# unicorn_1.net
KiCad netlist of a schematic drawn in Altium Designer
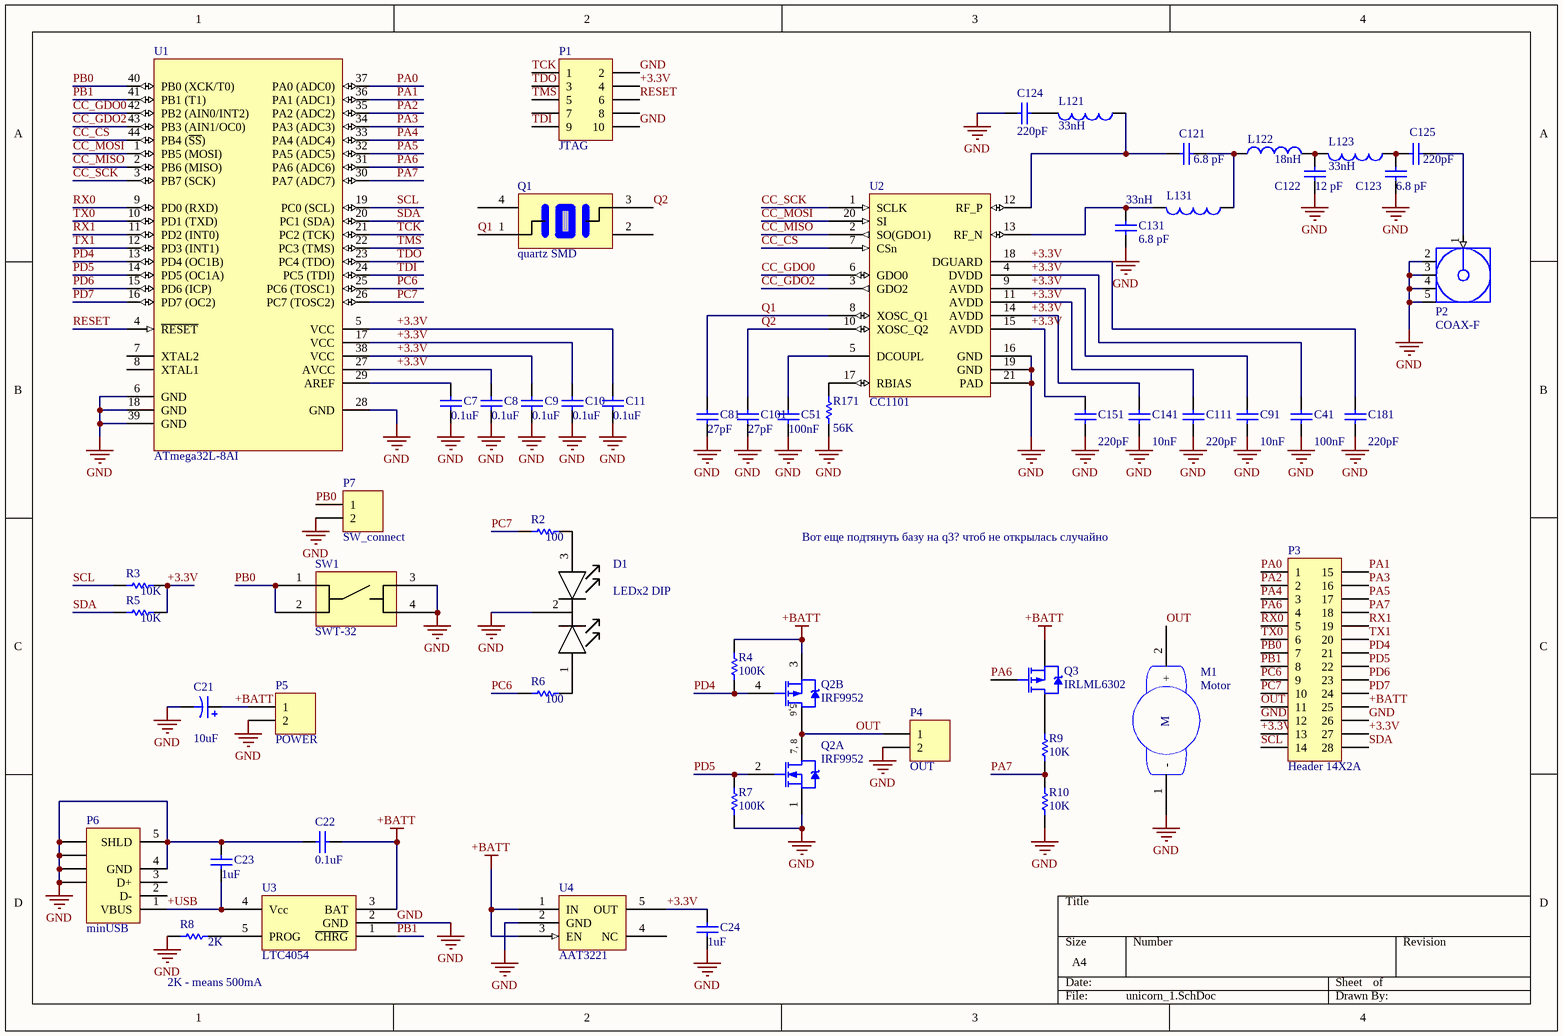
[diagram p0: unicorn_1.SchDoc]

(export (version "E")
  (design (tool "Eeschema 10.0.6"))
  (components
    (comp (ref "C7")
      (value "0.1uF")
      (footprint "CAPC1005L")
      (description "Capacitor (Semiconductor SIM Model)")
      (fields (field (name "PUBLISHER") "Altium Limited"))
      (libsource (lib "Miscellaneous Devices") (part "Cap Semi"))
    )
    (comp (ref "C8")
      (value "0.1uF")
      (footprint "CAPC1005L")
      (description "Capacitor (Semiconductor SIM Model)")
      (fields (field (name "PUBLISHER") "Altium Limited"))
      (libsource (lib "Miscellaneous Devices") (part "Cap Semi"))
    )
    (comp (ref "C9")
      (value "0.1uF")
      (footprint "CAPC1005L")
      (description "Capacitor (Semiconductor SIM Model)")
      (fields (field (name "PUBLISHER") "Altium Limited"))
      (libsource (lib "Miscellaneous Devices") (part "Cap Semi"))
    )
    (comp (ref "C10")
      (value "0.1uF")
      (footprint "CAPC1005L")
      (description "Capacitor (Semiconductor SIM Model)")
      (fields (field (name "PUBLISHER") "Altium Limited"))
      (libsource (lib "Miscellaneous Devices") (part "Cap Semi"))
    )
    (comp (ref "C11")
      (value "0.1uF")
      (footprint "CAPC1005L")
      (description "Capacitor (Semiconductor SIM Model)")
      (fields (field (name "PUBLISHER") "Altium Limited"))
      (libsource (lib "Miscellaneous Devices") (part "Cap Semi"))
    )
    (comp (ref "C21")
      (value "10uF")
      (footprint "CAPC2012L")
      (description "Polarized Capacitor (Surface Mount)")
      (fields (field (name "PUBLISHER") "Altium Limited"))
      (libsource (lib "Miscellaneous Devices") (part "Cap Pol3"))
    )
    (comp (ref "C22")
      (value "0.1uF")
      (footprint "CAPC1005L")
      (description "Capacitor (Semiconductor SIM Model)")
      (fields (field (name "PUBLISHER") "Altium Limited"))
      (libsource (lib "Miscellaneous Devices") (part "Cap Semi"))
    )
    (comp (ref "C23")
      (value "1uF")
      (footprint "CAPC1608L")
      (description "Capacitor (Semiconductor SIM Model)")
      (fields (field (name "PUBLISHER") "Altium Limited"))
      (libsource (lib "Miscellaneous Devices") (part "Cap Semi"))
    )
    (comp (ref "C24")
      (value "1uF")
      (footprint "CAPC1608L")
      (description "Capacitor (Semiconductor SIM Model)")
      (fields (field (name "PUBLISHER") "Altium Limited"))
      (libsource (lib "Miscellaneous Devices") (part "Cap Semi"))
    )
    (comp (ref "C41")
      (value "100nF")
      (footprint "CAPC1005L")
      (description "Capacitor (Semiconductor SIM Model)")
      (fields (field (name "PUBLISHER") "Altium Limited"))
      (libsource (lib "Miscellaneous Devices") (part "Cap Semi"))
    )
    (comp (ref "C51")
      (value "100nF")
      (footprint "CAPC1005L")
      (description "Capacitor (Semiconductor SIM Model)")
      (fields (field (name "PUBLISHER") "Altium Limited"))
      (libsource (lib "Miscellaneous Devices") (part "Cap Semi"))
    )
    (comp (ref "C81")
      (value "27pF")
      (footprint "CAPC1005L")
      (description "Capacitor (Semiconductor SIM Model)")
      (fields (field (name "PUBLISHER") "Altium Limited"))
      (libsource (lib "Miscellaneous Devices") (part "Cap Semi"))
    )
    (comp (ref "C91")
      (value "10nF")
      (footprint "CAPC1005L")
      (description "Capacitor (Semiconductor SIM Model)")
      (fields (field (name "PUBLISHER") "Altium Limited"))
      (libsource (lib "Miscellaneous Devices") (part "Cap Semi"))
    )
    (comp (ref "C101")
      (value "27pF")
      (footprint "CAPC1005L")
      (description "Capacitor (Semiconductor SIM Model)")
      (fields (field (name "PUBLISHER") "Altium Limited"))
      (libsource (lib "Miscellaneous Devices") (part "Cap Semi"))
    )
    (comp (ref "C111")
      (value "220pF")
      (footprint "CAPC1005L")
      (description "Capacitor (Semiconductor SIM Model)")
      (fields (field (name "PUBLISHER") "Altium Limited"))
      (libsource (lib "Miscellaneous Devices") (part "Cap Semi"))
    )
    (comp (ref "C121")
      (value "6.8 pF")
      (footprint "CAPC1005L")
      (description "Capacitor (Semiconductor SIM Model)")
      (fields (field (name "PUBLISHER") "Altium Limited"))
      (libsource (lib "Miscellaneous Devices") (part "Cap Semi"))
    )
    (comp (ref "C122")
      (value "12 pF")
      (footprint "CAPC1005L")
      (description "Capacitor (Semiconductor SIM Model)")
      (fields (field (name "PUBLISHER") "Altium Limited"))
      (libsource (lib "Miscellaneous Devices") (part "Cap Semi"))
    )
    (comp (ref "C123")
      (value "6.8 pF")
      (footprint "CAPC1005L")
      (description "Capacitor (Semiconductor SIM Model)")
      (fields (field (name "PUBLISHER") "Altium Limited"))
      (libsource (lib "Miscellaneous Devices") (part "Cap Semi"))
    )
    (comp (ref "C124")
      (value "220pF")
      (footprint "CAPC1005L")
      (description "Capacitor (Semiconductor SIM Model)")
      (fields (field (name "PUBLISHER") "Altium Limited"))
      (libsource (lib "Miscellaneous Devices") (part "Cap Semi"))
    )
    (comp (ref "C125")
      (value "220pF")
      (footprint "CAPC1005L")
      (description "Capacitor (Semiconductor SIM Model)")
      (fields (field (name "PUBLISHER") "Altium Limited"))
      (libsource (lib "Miscellaneous Devices") (part "Cap Semi"))
    )
    (comp (ref "C131")
      (value "6.8 pF")
      (footprint "CAPC1005L")
      (description "Capacitor (Semiconductor SIM Model)")
      (fields (field (name "PUBLISHER") "Altium Limited"))
      (libsource (lib "Miscellaneous Devices") (part "Cap Semi"))
    )
    (comp (ref "C141")
      (value "10nF")
      (footprint "CAPC1005L")
      (description "Capacitor (Semiconductor SIM Model)")
      (fields (field (name "PUBLISHER") "Altium Limited"))
      (libsource (lib "Miscellaneous Devices") (part "Cap Semi"))
    )
    (comp (ref "C151")
      (value "220pF")
      (footprint "CAPC1005L")
      (description "Capacitor (Semiconductor SIM Model)")
      (fields (field (name "PUBLISHER") "Altium Limited"))
      (libsource (lib "Miscellaneous Devices") (part "Cap Semi"))
    )
    (comp (ref "C181")
      (value "220pF")
      (footprint "CAPC1005L")
      (description "Capacitor (Semiconductor SIM Model)")
      (fields (field (name "PUBLISHER") "Altium Limited"))
      (libsource (lib "Miscellaneous Devices") (part "Cap Semi"))
    )
    (comp (ref "D1")
      (value "LEDx2 DIP")
      (footprint "LEDx2")
      (description "in DIP")
      (libsource (lib "uni_Library") (part "LEDx2"))
    )
    (comp (ref "L121")
      (value "33nH")
      (footprint "INDC1005AL")
      (description "Inductor")
      (fields (field (name "PUBLISHER") "Altium Limited"))
      (libsource (lib "Miscellaneous Devices") (part "Inductor"))
    )
    (comp (ref "L122")
      (value "18nH")
      (footprint "INDC1005AL")
      (description "Inductor")
      (fields (field (name "PUBLISHER") "Altium Limited"))
      (libsource (lib "Miscellaneous Devices") (part "Inductor"))
    )
    (comp (ref "L123")
      (value "33nH")
      (footprint "INDC1005AL")
      (description "Inductor")
      (fields (field (name "PUBLISHER") "Altium Limited"))
      (libsource (lib "Miscellaneous Devices") (part "Inductor"))
    )
    (comp (ref "L131")
      (value "33nH")
      (footprint "INDC1005AL")
      (description "Inductor")
      (fields (field (name "PUBLISHER") "Altium Limited"))
      (libsource (lib "Miscellaneous Devices") (part "Inductor"))
    )
    (comp (ref "M1") (value "Motor") (footprint "Motor") (libsource (lib "uni_Library") (part "Motor")))
    (comp (ref "P1")
      (value "JTAG")
      (footprint "HDR2X5")
      (description "Header, 5-Pin, Dual row")
      (fields (field (name "PUBLISHER") "Altium Limited"))
      (libsource (lib "Miscellaneous Connectors") (part "Header 5X2"))
    )
    (comp (ref "P2")
      (value "COAX-F")
      (footprint "MCX5.08-H5")
      (fields (field (name "PUBLISHER") "Altium Limited"))
      (libsource (lib "Miscellaneous Connectors") (part "COAX-F"))
    )
    (comp (ref "P3")
      (value "Header 14X2A")
      (footprint "HDR2X14_CEN")
      (description "Header, 14-Pin, Dual row")
      (fields (field (name "PUBLISHER") "Altium Limited"))
      (libsource (lib "Miscellaneous Connectors") (part "Header 14X2A"))
    )
    (comp (ref "P4")
      (value "OUT")
      (footprint "HDR1X2H")
      (description "Header, 2-Pin, Right Angle")
      (fields (field (name "PUBLISHER") "Altium Limited"))
      (libsource (lib "Miscellaneous Connectors") (part "Header 2H"))
    )
    (comp (ref "P5")
      (value "POWER")
      (footprint "HDR1X2H")
      (description "Header, 2-Pin, Right Angle")
      (fields (field (name "PUBLISHER") "Altium Limited"))
      (libsource (lib "Miscellaneous Connectors") (part "Header 2H"))
    )
    (comp (ref "P6")
      (value "minUSB")
      (footprint "440479")
      (description "USB 2.0, Right Angle, SMT, A Type, Receptacle, 5 Position, Black")
      (fields (field (name "PUBLISHER") "Altium Limited"))
      (libsource (lib "AMP Serial Bus USB") (part "440478-2"))
    )
    (comp (ref "P7")
      (value "SW_connect")
      (footprint "HDR1X2")
      (description "Header, 2-Pin")
      (fields (field (name "PUBLISHER") "Altium Limited"))
      (libsource (lib "Miscellaneous Connectors") (part "Header 2"))
    )
    (comp (ref "Q1")
      (value "quartz SMD")
      (footprint "quartz_pattern")
      (description "в корпусе 0532")
      (libsource (lib "uni_Library") (part "qartz 0532"))
    )
    (comp (ref "Q2")
      (value "IRF9952")
      (footprint "SO-8_N")
      (description "HEXFET Power MOSFET")
      (fields (field (name "PUBLISHER") "Altium Limited"))
      (libsource (lib "IR Discrete MOSFET - Power") (part "IRF9952"))
    )
    (comp (ref "Q3")
      (value "IRLML6302")
      (footprint "SOT-23")
      (description "HEXFET Power MOSFET")
      (fields (field (name "PUBLISHER") "Altium Limited"))
      (libsource (lib "IR Discrete MOSFET - Power") (part "IRLML6302"))
    )
    (comp (ref "R2")
      (value "100")
      (footprint "RESC1005L")
      (description "Semiconductor Resistor")
      (fields (field (name "PUBLISHER") "Altium Limited"))
      (libsource (lib "Miscellaneous Devices") (part "Res Semi"))
    )
    (comp (ref "R3")
      (value "10K")
      (footprint "RESC1005L")
      (description "Semiconductor Resistor")
      (fields (field (name "PUBLISHER") "Altium Limited"))
      (libsource (lib "Miscellaneous Devices") (part "Res Semi"))
    )
    (comp (ref "R4")
      (value "100K")
      (footprint "RESC1005L")
      (description "Semiconductor Resistor")
      (fields (field (name "PUBLISHER") "Altium Limited"))
      (libsource (lib "Miscellaneous Devices") (part "Res Semi"))
    )
    (comp (ref "R5")
      (value "10K")
      (footprint "RESC1005L")
      (description "Semiconductor Resistor")
      (fields (field (name "PUBLISHER") "Altium Limited"))
      (libsource (lib "Miscellaneous Devices") (part "Res Semi"))
    )
    (comp (ref "R6")
      (value "100")
      (footprint "RESC1005L")
      (description "Semiconductor Resistor")
      (fields (field (name "PUBLISHER") "Altium Limited"))
      (libsource (lib "Miscellaneous Devices") (part "Res Semi"))
    )
    (comp (ref "R7")
      (value "100K")
      (footprint "RESC1005L")
      (description "Semiconductor Resistor")
      (fields (field (name "PUBLISHER") "Altium Limited"))
      (libsource (lib "Miscellaneous Devices") (part "Res Semi"))
    )
    (comp (ref "R8")
      (value "2K")
      (footprint "RESC1005L")
      (description "Semiconductor Resistor")
      (fields (field (name "PUBLISHER") "Altium Limited"))
      (libsource (lib "Miscellaneous Devices") (part "Res Semi"))
    )
    (comp (ref "R9")
      (value "10K")
      (footprint "RESC1005L")
      (description "Semiconductor Resistor")
      (fields (field (name "PUBLISHER") "Altium Limited"))
      (libsource (lib "Miscellaneous Devices") (part "Res Semi"))
    )
    (comp (ref "R10")
      (value "10K")
      (footprint "RESC1005L")
      (description "Semiconductor Resistor")
      (fields (field (name "PUBLISHER") "Altium Limited"))
      (libsource (lib "Miscellaneous Devices") (part "Res Semi"))
    )
    (comp (ref "R171")
      (value "56K")
      (footprint "RESC1005L")
      (description "Semiconductor Resistor")
      (fields (field (name "PUBLISHER") "Altium Limited"))
      (libsource (lib "Miscellaneous Devices") (part "Res Semi"))
    )
    (comp (ref "SW1")
      (value "SWT-32")
      (footprint "SWT-32 pattern")
      (description "Кнопка тактова , поверхностный монтаж")
      (libsource (lib "uni_Library") (part "SWT-32"))
    )
    (comp (ref "U1")
      (value "ATmega32L-8AI")
      (footprint "44A_L")
      (description "8-Bit AVR Microcontroller with 32K Bytes of In-System Programmable Flash Memory")
      (fields (field (name "PUBLISHER") "Altium Limited"))
      (libsource (lib "Atmel Microcontroller 8-Bit AVR") (part "ATmega32L-8AI"))
    )
    (comp (ref "U2")
      (value "CC1101")
      (footprint "QFN50P397X397X80-20N")
      (description "Low-Power Sub-1 GHz RF Transceiver")
      (libsource (lib "uni_Library") (part "CC1101"))
    )
    (comp (ref "U3")
      (value "LTC4054")
      (footprint "SOT95P270X100-5N")
      (description "Standalone Linear  Li-Ion Battery Charger with  Thermal Regulation in ThinSOT")
      (libsource (lib "uni_Library") (part "LTC4054"))
    )
    (comp (ref "U4")
      (value "AAT3221")
      (footprint "SOT95P280X145-5N")
      (description "PowerLinear NanoPower low   dropout (LDO) linear regulator.")
      (libsource (lib "uni_Library") (part "AAT3221"))
    )
  )
  (nets
    (net (code "1") (name "+BATT") (class "Default")
      (node (ref "C21") (pin "1") (pinfunction "1_1") (pintype "passive"))
      (node (ref "C22") (pin "2") (pinfunction "2_2") (pintype "passive"))
      (node (ref "P3") (pin "25") (pinfunction "25_25") (pintype "passive"))
      (node (ref "P5") (pin "1") (pinfunction "1_1") (pintype "passive"))
      (node (ref "Q2") (pin "3") (pinfunction "S2_3") (pintype "passive"))
      (node (ref "Q3") (pin "2") (pinfunction "S_2") (pintype "passive"))
      (node (ref "R4") (pin "1") (pinfunction "1_1") (pintype "passive"))
      (node (ref "U3") (pin "3") (pinfunction "BAT_3") (pintype "passive"))
      (node (ref "U4") (pin "1") (pinfunction "IN_1") (pintype "power_in"))
      (node (ref "U4") (pin "3") (pinfunction "EN_3") (pintype "input"))
    )
    (net (code "2") (name "/+3.3V") (class "Default")
      (node (ref "C10") (pin "1") (pinfunction "1_1") (pintype "passive"))
      (node (ref "C11") (pin "1") (pinfunction "1_1") (pintype "passive"))
      (node (ref "C111") (pin "2") (pinfunction "2_2") (pintype "passive"))
      (node (ref "C141") (pin "2") (pinfunction "2_2") (pintype "passive"))
      (node (ref "C151") (pin "2") (pinfunction "2_2") (pintype "passive"))
      (node (ref "C181") (pin "2") (pinfunction "2_2") (pintype "passive"))
      (node (ref "C24") (pin "1") (pinfunction "1_1") (pintype "passive"))
      (node (ref "C41") (pin "2") (pinfunction "2_2") (pintype "passive"))
      (node (ref "C8") (pin "1") (pinfunction "1_1") (pintype "passive"))
      (node (ref "C9") (pin "1") (pinfunction "1_1") (pintype "passive"))
      (node (ref "C91") (pin "2") (pinfunction "2_2") (pintype "passive"))
      (node (ref "P1") (pin "4") (pinfunction "4_4") (pintype "passive"))
      (node (ref "P3") (pin "13") (pinfunction "13_13") (pintype "passive"))
      (node (ref "P3") (pin "27") (pinfunction "27_27") (pintype "passive"))
      (node (ref "R3") (pin "1") (pinfunction "1_1") (pintype "passive"))
      (node (ref "R5") (pin "1") (pinfunction "1_1") (pintype "passive"))
      (node (ref "U1") (pin "17") (pinfunction "VCC_17") (pintype "power_in"))
      (node (ref "U1") (pin "27") (pinfunction "AVCC_27") (pintype "power_in"))
      (node (ref "U1") (pin "38") (pinfunction "VCC_38") (pintype "power_in"))
      (node (ref "U1") (pin "5") (pinfunction "VCC_5") (pintype "power_in"))
      (node (ref "U2") (pin "11") (pinfunction "AVDD_11") (pintype "power_in"))
      (node (ref "U2") (pin "14") (pinfunction "AVDD_14") (pintype "power_in"))
      (node (ref "U2") (pin "15") (pinfunction "AVDD_15") (pintype "power_in"))
      (node (ref "U2") (pin "18") (pinfunction "DGUARD_18") (pintype "power_in"))
      (node (ref "U2") (pin "4") (pinfunction "DVDD_4") (pintype "power_in"))
      (node (ref "U2") (pin "9") (pinfunction "AVDD_9") (pintype "power_in"))
      (node (ref "U4") (pin "5") (pinfunction "OUT_5") (pintype "power_in"))
    )
    (net (code "3") (name "/+USB") (class "Default")
      (node (ref "C23") (pin "2") (pinfunction "2_2") (pintype "passive"))
      (node (ref "P6") (pin "1") (pinfunction "VBUS_1") (pintype "power_in"))
      (node (ref "U3") (pin "4") (pinfunction "Vcc_4") (pintype "passive"))
    )
    (net (code "4") (name "/CC_CS") (class "Default")
      (node (ref "U1") (pin "44") (pinfunction "PB4_(~{SS})_44") (pintype "bidirectional"))
      (node (ref "U2") (pin "7") (pinfunction "CSn_7") (pintype "input"))
    )
    (net (code "5") (name "/CC_GDO0") (class "Default")
      (node (ref "U1") (pin "42") (pinfunction "PB2_(AIN0/INT2)_42") (pintype "bidirectional"))
      (node (ref "U2") (pin "6") (pinfunction "GDO0_6") (pintype "bidirectional"))
    )
    (net (code "6") (name "/CC_GDO2") (class "Default")
      (node (ref "U1") (pin "43") (pinfunction "PB3_(AIN1/OC0)_43") (pintype "bidirectional"))
      (node (ref "U2") (pin "3") (pinfunction "GDO2_3") (pintype "output"))
    )
    (net (code "7") (name "/CC_MISO") (class "Default")
      (node (ref "U1") (pin "2") (pinfunction "PB6_(MISO)_2") (pintype "bidirectional"))
      (node (ref "U2") (pin "2") (pinfunction "SO(GDO1)_2") (pintype "output"))
    )
    (net (code "8") (name "/CC_MOSI") (class "Default")
      (node (ref "U1") (pin "1") (pinfunction "PB5_(MOSI)_1") (pintype "bidirectional"))
      (node (ref "U2") (pin "20") (pinfunction "SI_20") (pintype "input"))
    )
    (net (code "9") (name "/CC_SCK") (class "Default")
      (node (ref "U1") (pin "3") (pinfunction "PB7_(SCK)_3") (pintype "bidirectional"))
      (node (ref "U2") (pin "1") (pinfunction "SCLK_1") (pintype "input"))
    )
    (net (code "10") (name "/OUT") (class "Default")
      (node (ref "M1") (pin "2") (pinfunction "+_2") (pintype "passive"))
      (node (ref "P3") (pin "11") (pinfunction "11_11") (pintype "passive"))
      (node (ref "P4") (pin "1") (pinfunction "1_1") (pintype "passive"))
      (node (ref "Q2") (pin "5") (pinfunction "D2_5") (pintype "passive"))
      (node (ref "Q2") (pin "6") (pinfunction "D2_6") (pintype "passive"))
      (node (ref "Q2") (pin "7") (pinfunction "D1_7") (pintype "passive"))
      (node (ref "Q2") (pin "8") (pinfunction "D1_8") (pintype "passive"))
    )
    (net (code "11") (name "/PA0") (class "Default")
      (node (ref "P3") (pin "1") (pinfunction "1_1") (pintype "passive"))
      (node (ref "U1") (pin "37") (pinfunction "PA0_(ADC0)_37") (pintype "bidirectional"))
    )
    (net (code "12") (name "/PA1") (class "Default")
      (node (ref "P3") (pin "15") (pinfunction "15_15") (pintype "passive"))
      (node (ref "U1") (pin "36") (pinfunction "PA1_(ADC1)_36") (pintype "bidirectional"))
    )
    (net (code "13") (name "/PA2") (class "Default")
      (node (ref "P3") (pin "2") (pinfunction "2_2") (pintype "passive"))
      (node (ref "U1") (pin "35") (pinfunction "PA2_(ADC2)_35") (pintype "bidirectional"))
    )
    (net (code "14") (name "/PA3") (class "Default")
      (node (ref "P3") (pin "16") (pinfunction "16_16") (pintype "passive"))
      (node (ref "U1") (pin "34") (pinfunction "PA3_(ADC3)_34") (pintype "bidirectional"))
    )
    (net (code "15") (name "/PA4") (class "Default")
      (node (ref "P3") (pin "3") (pinfunction "3_3") (pintype "passive"))
      (node (ref "U1") (pin "33") (pinfunction "PA4_(ADC4)_33") (pintype "bidirectional"))
    )
    (net (code "16") (name "/PA5") (class "Default")
      (node (ref "P3") (pin "17") (pinfunction "17_17") (pintype "passive"))
      (node (ref "U1") (pin "32") (pinfunction "PA5_(ADC5)_32") (pintype "bidirectional"))
    )
    (net (code "17") (name "/PA6") (class "Default")
      (node (ref "P3") (pin "4") (pinfunction "4_4") (pintype "passive"))
      (node (ref "Q3") (pin "1") (pinfunction "G_1") (pintype "passive"))
      (node (ref "U1") (pin "31") (pinfunction "PA6_(ADC6)_31") (pintype "bidirectional"))
    )
    (net (code "18") (name "/PA7") (class "Default")
      (node (ref "P3") (pin "18") (pinfunction "18_18") (pintype "passive"))
      (node (ref "R10") (pin "1") (pinfunction "1_1") (pintype "passive"))
      (node (ref "R9") (pin "2") (pinfunction "2_2") (pintype "passive"))
      (node (ref "U1") (pin "30") (pinfunction "PA7_(ADC7)_30") (pintype "bidirectional"))
    )
    (net (code "19") (name "/PB0") (class "Default")
      (node (ref "P3") (pin "7") (pinfunction "7_7") (pintype "passive"))
      (node (ref "P7") (pin "1") (pinfunction "1_1") (pintype "passive"))
      (node (ref "SW1") (pin "1") (pintype "passive"))
      (node (ref "SW1") (pin "2") (pintype "passive"))
      (node (ref "U1") (pin "40") (pinfunction "PB0_(XCK/T0)_40") (pintype "bidirectional"))
    )
    (net (code "20") (name "/PB1") (class "Default")
      (node (ref "P3") (pin "8") (pinfunction "8_8") (pintype "passive"))
      (node (ref "U1") (pin "41") (pinfunction "PB1_(T1)_41") (pintype "bidirectional"))
      (node (ref "U3") (pin "1") (pinfunction "~{CHRG}_1") (pintype "passive"))
    )
    (net (code "21") (name "/PC6") (class "Default")
      (node (ref "P3") (pin "9") (pinfunction "9_9") (pintype "passive"))
      (node (ref "R6") (pin "2") (pinfunction "2_2") (pintype "passive"))
      (node (ref "U1") (pin "25") (pinfunction "PC6_(TOSC1)_25") (pintype "bidirectional"))
    )
    (net (code "22") (name "/PC7") (class "Default")
      (node (ref "P3") (pin "10") (pinfunction "10_10") (pintype "passive"))
      (node (ref "R2") (pin "2") (pinfunction "2_2") (pintype "passive"))
      (node (ref "U1") (pin "26") (pinfunction "PC7_(TOSC2)_26") (pintype "bidirectional"))
    )
    (net (code "23") (name "/PD4") (class "Default")
      (node (ref "P3") (pin "21") (pinfunction "21_21") (pintype "passive"))
      (node (ref "Q2") (pin "4") (pinfunction "G2_4") (pintype "passive"))
      (node (ref "R4") (pin "2") (pinfunction "2_2") (pintype "passive"))
      (node (ref "U1") (pin "13") (pinfunction "PD4_(OC1B)_13") (pintype "bidirectional"))
    )
    (net (code "24") (name "/PD5") (class "Default")
      (node (ref "P3") (pin "22") (pinfunction "22_22") (pintype "passive"))
      (node (ref "Q2") (pin "2") (pinfunction "G1_2") (pintype "passive"))
      (node (ref "R7") (pin "1") (pinfunction "1_1") (pintype "passive"))
      (node (ref "U1") (pin "14") (pinfunction "PD5_(OC1A)_14") (pintype "bidirectional"))
    )
    (net (code "25") (name "/PD6") (class "Default")
      (node (ref "P3") (pin "23") (pinfunction "23_23") (pintype "passive"))
      (node (ref "U1") (pin "15") (pinfunction "PD6_(ICP)_15") (pintype "bidirectional"))
    )
    (net (code "26") (name "/PD7") (class "Default")
      (node (ref "P3") (pin "24") (pinfunction "24_24") (pintype "passive"))
      (node (ref "U1") (pin "16") (pinfunction "PD7_(OC2)_16") (pintype "bidirectional"))
    )
    (net (code "27") (name "/Q1") (class "Default")
      (node (ref "C81") (pin "2") (pinfunction "2_2") (pintype "passive"))
      (node (ref "Q1") (pin "1") (pintype "passive"))
      (node (ref "U2") (pin "8") (pinfunction "XOSC_Q1_8") (pintype "bidirectional"))
    )
    (net (code "28") (name "/Q2") (class "Default")
      (node (ref "C101") (pin "2") (pinfunction "2_2") (pintype "passive"))
      (node (ref "Q1") (pin "3") (pintype "passive"))
      (node (ref "U2") (pin "10") (pinfunction "XOSC_Q2_10") (pintype "bidirectional"))
    )
    (net (code "29") (name "/RESET") (class "Default")
      (node (ref "P1") (pin "6") (pinfunction "6_6") (pintype "passive"))
      (node (ref "U1") (pin "4") (pinfunction "~{RESET}_4") (pintype "input"))
    )
    (net (code "30") (name "/RX0") (class "Default")
      (node (ref "P3") (pin "5") (pinfunction "5_5") (pintype "passive"))
      (node (ref "U1") (pin "9") (pinfunction "PD0_(RXD)_9") (pintype "bidirectional"))
    )
    (net (code "31") (name "/RX1") (class "Default")
      (node (ref "P3") (pin "19") (pinfunction "19_19") (pintype "passive"))
      (node (ref "U1") (pin "11") (pinfunction "PD2_(INT0)_11") (pintype "bidirectional"))
    )
    (net (code "32") (name "/SCL") (class "Default")
      (node (ref "P3") (pin "14") (pinfunction "14_14") (pintype "passive"))
      (node (ref "R3") (pin "2") (pinfunction "2_2") (pintype "passive"))
      (node (ref "U1") (pin "19") (pinfunction "PC0_(SCL)_19") (pintype "bidirectional"))
    )
    (net (code "33") (name "/SDA") (class "Default")
      (node (ref "P3") (pin "28") (pinfunction "28_28") (pintype "passive"))
      (node (ref "R5") (pin "2") (pinfunction "2_2") (pintype "passive"))
      (node (ref "U1") (pin "20") (pinfunction "PC1_(SDA)_20") (pintype "bidirectional"))
    )
    (net (code "34") (name "/TCK") (class "Default")
      (node (ref "P1") (pin "1") (pinfunction "1_1") (pintype "passive"))
      (node (ref "U1") (pin "21") (pinfunction "PC2_(TCK)_21") (pintype "bidirectional"))
    )
    (net (code "35") (name "/TDI") (class "Default")
      (node (ref "P1") (pin "9") (pinfunction "9_9") (pintype "passive"))
      (node (ref "U1") (pin "24") (pinfunction "PC5_(TDI)_24") (pintype "bidirectional"))
    )
    (net (code "36") (name "/TDO") (class "Default")
      (node (ref "P1") (pin "3") (pinfunction "3_3") (pintype "passive"))
      (node (ref "U1") (pin "23") (pinfunction "PC4_(TDO)_23") (pintype "bidirectional"))
    )
    (net (code "37") (name "/TMS") (class "Default")
      (node (ref "P1") (pin "5") (pinfunction "5_5") (pintype "passive"))
      (node (ref "U1") (pin "22") (pinfunction "PC3_(TMS)_22") (pintype "bidirectional"))
    )
    (net (code "38") (name "/TX0") (class "Default")
      (node (ref "P3") (pin "6") (pinfunction "6_6") (pintype "passive"))
      (node (ref "U1") (pin "10") (pinfunction "PD1_(TXD)_10") (pintype "bidirectional"))
    )
    (net (code "39") (name "/TX1") (class "Default")
      (node (ref "P3") (pin "20") (pinfunction "20_20") (pintype "passive"))
      (node (ref "U1") (pin "12") (pinfunction "PD3_(INT1)_12") (pintype "bidirectional"))
    )
    (net (code "40") (name "GND") (class "Default")
      (node (ref "C10") (pin "2") (pinfunction "2_2") (pintype "passive"))
      (node (ref "C101") (pin "1") (pinfunction "1_1") (pintype "passive"))
      (node (ref "C11") (pin "2") (pinfunction "2_2") (pintype "passive"))
      (node (ref "C111") (pin "1") (pinfunction "1_1") (pintype "passive"))
      (node (ref "C122") (pin "1") (pinfunction "1_1") (pintype "passive"))
      (node (ref "C123") (pin "1") (pinfunction "1_1") (pintype "passive"))
      (node (ref "C124") (pin "2") (pinfunction "2_2") (pintype "passive"))
      (node (ref "C131") (pin "2") (pinfunction "2_2") (pintype "passive"))
      (node (ref "C141") (pin "1") (pinfunction "1_1") (pintype "passive"))
      (node (ref "C151") (pin "1") (pinfunction "1_1") (pintype "passive"))
      (node (ref "C181") (pin "1") (pinfunction "1_1") (pintype "passive"))
      (node (ref "C21") (pin "2") (pinfunction "2_2") (pintype "passive"))
      (node (ref "C22") (pin "1") (pinfunction "1_1") (pintype "passive"))
      (node (ref "C23") (pin "1") (pinfunction "1_1") (pintype "passive"))
      (node (ref "C24") (pin "2") (pinfunction "2_2") (pintype "passive"))
      (node (ref "C41") (pin "1") (pinfunction "1_1") (pintype "passive"))
      (node (ref "C51") (pin "1") (pinfunction "1_1") (pintype "passive"))
      (node (ref "C7") (pin "2") (pinfunction "2_2") (pintype "passive"))
      (node (ref "C8") (pin "2") (pinfunction "2_2") (pintype "passive"))
      (node (ref "C81") (pin "1") (pinfunction "1_1") (pintype "passive"))
      (node (ref "C9") (pin "2") (pinfunction "2_2") (pintype "passive"))
      (node (ref "C91") (pin "1") (pinfunction "1_1") (pintype "passive"))
      (node (ref "D1") (pin "2") (pinfunction "GND_2") (pintype "passive"))
      (node (ref "M1") (pin "1") (pinfunction "-_1") (pintype "passive"))
      (node (ref "P1") (pin "10") (pinfunction "10_10") (pintype "passive"))
      (node (ref "P1") (pin "2") (pinfunction "2_2") (pintype "passive"))
      (node (ref "P2") (pin "2") (pinfunction "GND_2") (pintype "power_in"))
      (node (ref "P2") (pin "3") (pinfunction "GND_3") (pintype "power_in"))
      (node (ref "P2") (pin "4") (pinfunction "GND_4") (pintype "power_in"))
      (node (ref "P2") (pin "5") (pinfunction "GND_5") (pintype "power_in"))
      (node (ref "P3") (pin "12") (pinfunction "12_12") (pintype "passive"))
      (node (ref "P3") (pin "26") (pinfunction "26_26") (pintype "passive"))
      (node (ref "P4") (pin "2") (pinfunction "2_2") (pintype "passive"))
      (node (ref "P5") (pin "2") (pinfunction "2_2") (pintype "passive"))
      (node (ref "P6") (pin "4") (pinfunction "GND_4") (pintype "power_in"))
      (node (ref "P6") (pin "5") (pinfunction "SHLD_5") (pintype "passive"))
      (node (ref "P6") (pin "6") (pinfunction "SHLD_6") (pintype "passive"))
      (node (ref "P6") (pin "7") (pinfunction "SHLD_7") (pintype "passive"))
      (node (ref "P6") (pin "8") (pinfunction "SHLD_8") (pintype "passive"))
      (node (ref "P6") (pin "9") (pinfunction "SHLD_9") (pintype "passive"))
      (node (ref "P7") (pin "2") (pinfunction "2_2") (pintype "passive"))
      (node (ref "Q2") (pin "1") (pinfunction "S1_1") (pintype "passive"))
      (node (ref "R10") (pin "2") (pinfunction "2_2") (pintype "passive"))
      (node (ref "R171") (pin "1") (pinfunction "1_1") (pintype "passive"))
      (node (ref "R7") (pin "2") (pinfunction "2_2") (pintype "passive"))
      (node (ref "R8") (pin "2") (pinfunction "2_2") (pintype "passive"))
      (node (ref "SW1") (pin "3") (pintype "passive"))
      (node (ref "SW1") (pin "4") (pintype "passive"))
      (node (ref "U1") (pin "18") (pinfunction "GND_18") (pintype "power_in"))
      (node (ref "U1") (pin "28") (pinfunction "GND_28") (pintype "power_in"))
      (node (ref "U1") (pin "39") (pinfunction "GND_39") (pintype "power_in"))
      (node (ref "U1") (pin "6") (pinfunction "GND_6") (pintype "power_in"))
      (node (ref "U2") (pin "16") (pinfunction "GND_16") (pintype "power_in"))
      (node (ref "U2") (pin "19") (pinfunction "GND_19") (pintype "power_in"))
      (node (ref "U2") (pin "21") (pinfunction "PAD_21") (pintype "power_in"))
      (node (ref "U3") (pin "2") (pinfunction "GND_2") (pintype "passive"))
      (node (ref "U4") (pin "2") (pinfunction "GND_2") (pintype "power_in"))
    )
    (net (code "41") (name "Net-(C121-Pad1)") (class "Default")
      (node (ref "C121") (pin "1") (pinfunction "1_1") (pintype "passive"))
      (node (ref "L122") (pin "1") (pinfunction "1_1") (pintype "passive"))
      (node (ref "L131") (pin "1") (pinfunction "1_1") (pintype "passive"))
    )
    (net (code "42") (name "Net-(C122-Pad2)") (class "Default")
      (node (ref "C122") (pin "2") (pinfunction "2_2") (pintype "passive"))
      (node (ref "L122") (pin "2") (pinfunction "2_2") (pintype "passive"))
      (node (ref "L123") (pin "2") (pinfunction "2_2") (pintype "passive"))
    )
    (net (code "43") (name "Net-(C123-Pad2)") (class "Default")
      (node (ref "C123") (pin "2") (pinfunction "2_2") (pintype "passive"))
      (node (ref "C125") (pin "2") (pinfunction "2_2") (pintype "passive"))
      (node (ref "L123") (pin "1") (pinfunction "1_1") (pintype "passive"))
    )
    (net (code "44") (name "Net-(C124-Pad1)") (class "Default")
      (node (ref "C124") (pin "1") (pinfunction "1_1") (pintype "passive"))
      (node (ref "L121") (pin "2") (pinfunction "2_2") (pintype "passive"))
    )
    (net (code "45") (name "Net-(D1-G)") (class "Default")
      (node (ref "D1") (pin "1") (pinfunction "G_1") (pintype "passive"))
      (node (ref "R6") (pin "1") (pinfunction "1_1") (pintype "passive"))
    )
    (net (code "46") (name "Net-(D1-R)") (class "Default")
      (node (ref "D1") (pin "3") (pinfunction "R_3") (pintype "passive"))
      (node (ref "R2") (pin "1") (pinfunction "1_1") (pintype "passive"))
    )
    (net (code "47") (name "Net-(P2-Signal)") (class "Default")
      (node (ref "C125") (pin "1") (pinfunction "1_1") (pintype "passive"))
      (node (ref "P2") (pin "1") (pinfunction "Signal_1") (pintype "input"))
    )
    (net (code "48") (name "Net-(Q3-D)") (class "Default")
      (node (ref "Q3") (pin "3") (pinfunction "D_3") (pintype "passive"))
      (node (ref "R9") (pin "1") (pinfunction "1_1") (pintype "passive"))
    )
    (net (code "49") (name "Net-(U1-AREF)") (class "Default")
      (node (ref "C7") (pin "1") (pinfunction "1_1") (pintype "passive"))
      (node (ref "U1") (pin "29") (pinfunction "AREF_29") (pintype "passive"))
    )
    (net (code "50") (name "Net-(U2-DCOUPL)") (class "Default")
      (node (ref "C51") (pin "2") (pinfunction "2_2") (pintype "passive"))
      (node (ref "U2") (pin "5") (pinfunction "DCOUPL_5") (pintype "power_in"))
    )
    (net (code "51") (name "Net-(U2-RBIAS)") (class "Default")
      (node (ref "R171") (pin "2") (pinfunction "2_2") (pintype "passive"))
      (node (ref "U2") (pin "17") (pinfunction "RBIAS_17") (pintype "bidirectional"))
    )
    (net (code "52") (name "Net-(U2-RF_N)") (class "Default")
      (node (ref "C131") (pin "1") (pinfunction "1_1") (pintype "passive"))
      (node (ref "L131") (pin "2") (pinfunction "2_2") (pintype "passive"))
      (node (ref "U2") (pin "13") (pinfunction "RF_N_13") (pintype "bidirectional"))
    )
    (net (code "53") (name "Net-(U2-RF_P)") (class "Default")
      (node (ref "C121") (pin "2") (pinfunction "2_2") (pintype "passive"))
      (node (ref "L121") (pin "1") (pinfunction "1_1") (pintype "passive"))
      (node (ref "U2") (pin "12") (pinfunction "RF_P_12") (pintype "bidirectional"))
    )
    (net (code "54") (name "Net-(U3-PROG)") (class "Default")
      (node (ref "R8") (pin "1") (pinfunction "1_1") (pintype "passive"))
      (node (ref "U3") (pin "5") (pinfunction "PROG_5") (pintype "passive"))
    )
    (net (code "55") (name "unconnected-(P1-Pad7)") (class "Default")
      (node (ref "P1") (pin "7") (pinfunction "7_7") (pintype "passive"))
    )
    (net (code "56") (name "unconnected-(P1-Pad8)") (class "Default")
      (node (ref "P1") (pin "8") (pinfunction "8_8") (pintype "passive"))
    )
    (net (code "57") (name "unconnected-(P6-D+-Pad3)") (class "Default")
      (node (ref "P6") (pin "3") (pinfunction "D+_3") (pintype "passive"))
    )
    (net (code "58") (name "unconnected-(P6-D--Pad2)") (class "Default")
      (node (ref "P6") (pin "2") (pinfunction "D-_2") (pintype "passive"))
    )
    (net (code "59") (name "unconnected-(Q1-Pad2)") (class "Default")
      (node (ref "Q1") (pin "2") (pintype "passive"))
    )
    (net (code "60") (name "unconnected-(Q1-Pad4)") (class "Default")
      (node (ref "Q1") (pin "4") (pintype "passive"))
    )
    (net (code "61") (name "unconnected-(U1-XTAL1-Pad8)") (class "Default")
      (node (ref "U1") (pin "8") (pinfunction "XTAL1_8") (pintype "passive"))
    )
    (net (code "62") (name "unconnected-(U1-XTAL2-Pad7)") (class "Default")
      (node (ref "U1") (pin "7") (pinfunction "XTAL2_7") (pintype "passive"))
    )
    (net (code "63") (name "unconnected-(U4-NC-Pad4)") (class "Default")
      (node (ref "U4") (pin "4") (pinfunction "NC_4") (pintype "passive"))
    )
  )
)
